# Pololu_Magnetic_Encoder.net
KiCad netlist of a schematic drawn in EAGLE
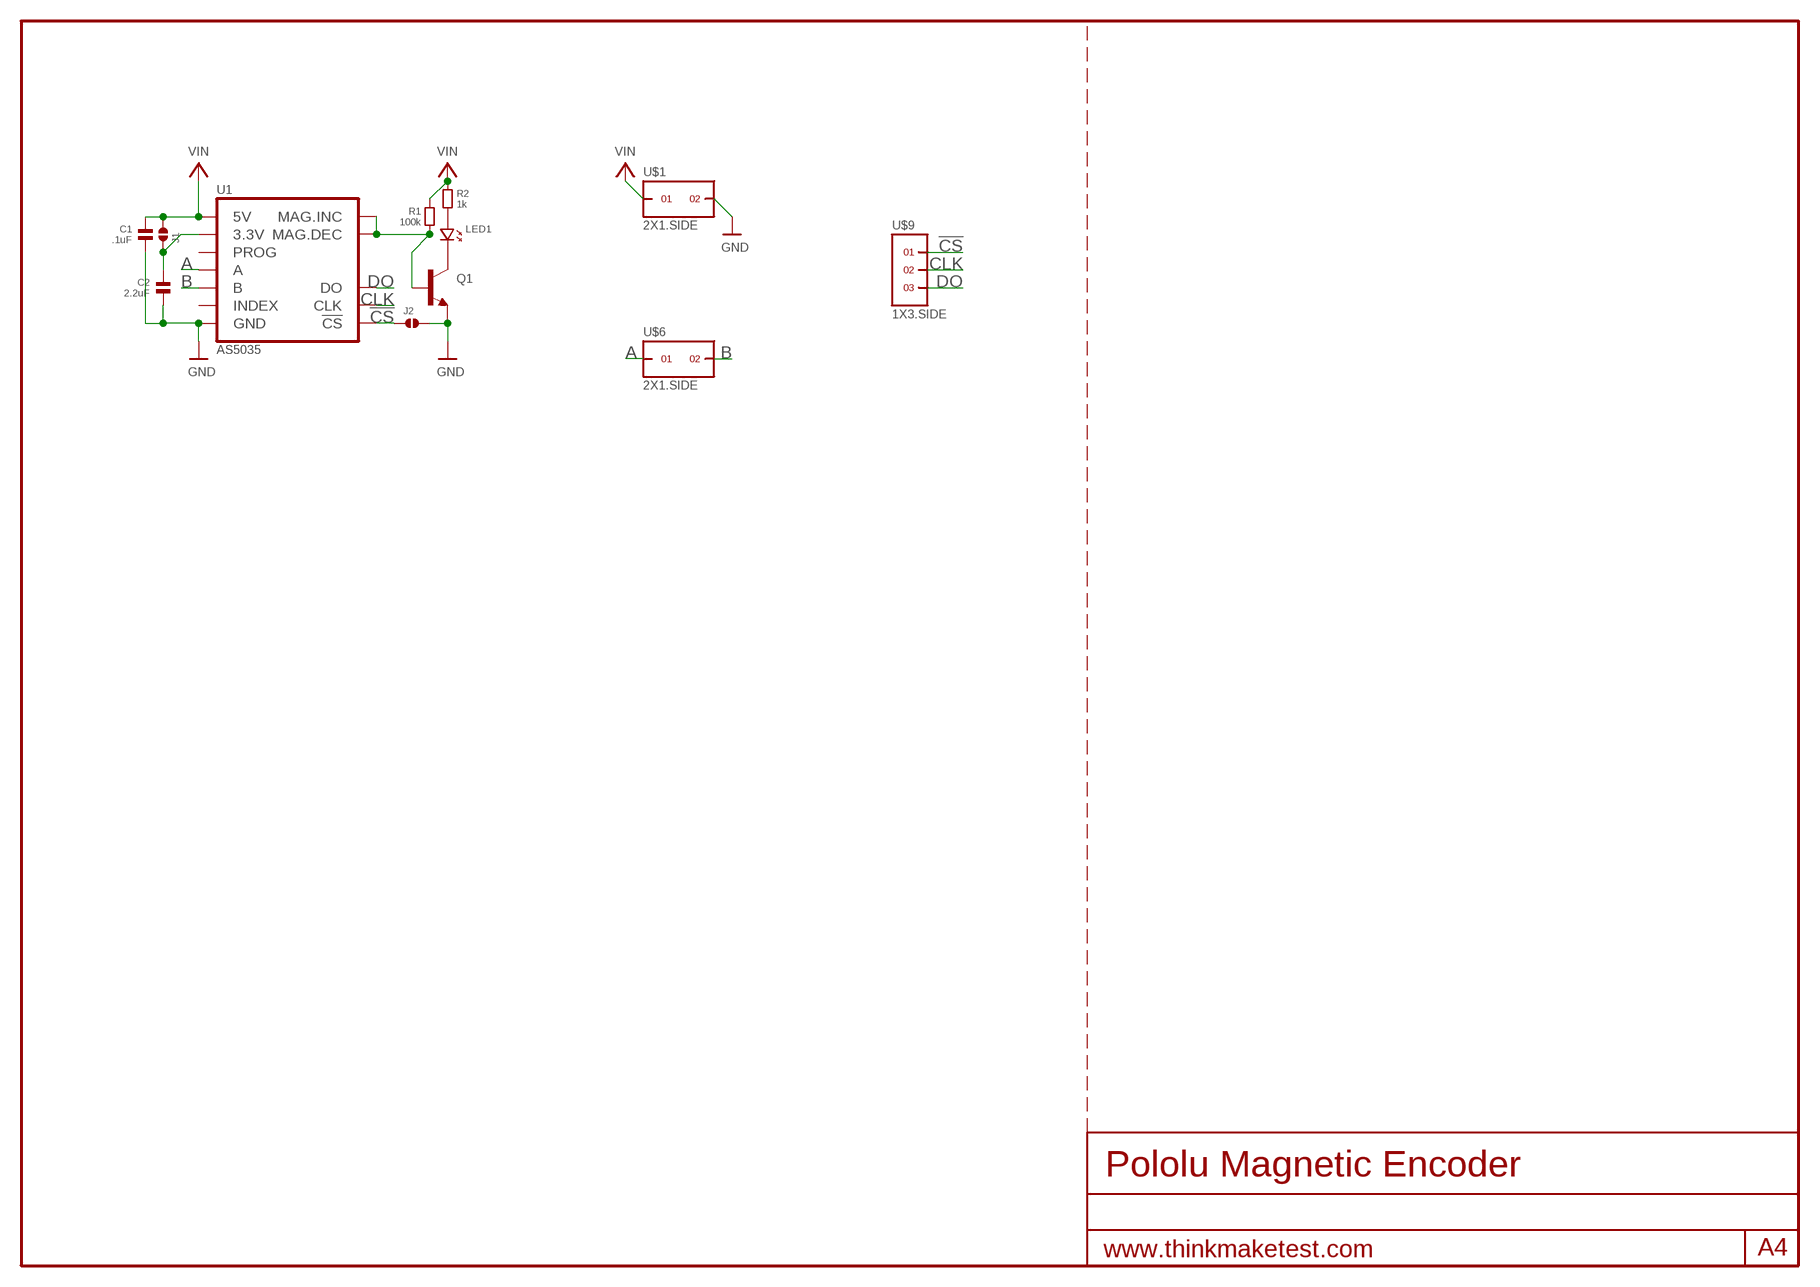
[diagram p0: schematic, sheet 1]

(export (version "E")
  (design (tool "Eeschema 10.0.6"))
  (components
    (comp (ref "C1")
      (value ".1uF")
      (footprint "eagle-import:0603")
      (libsource (lib "eagle-import") (part "CAPACITOR.0603"))
    )
    (comp (ref "C2")
      (value "2.2uF")
      (footprint "eagle-import:0603")
      (libsource (lib "eagle-import") (part "CAPACITOR.0603"))
    )
    (comp (ref "J1")
      (value "SOLDERJUMPER.2.LRG.PASTE")
      (footprint "eagle-import:2.LRG.PASTE")
      (libsource (lib "eagle-import") (part "SOLDERJUMPER.2.LRG.PASTE"))
    )
    (comp (ref "J2")
      (value "SOLDERJUMPER.2.LRG.PASTE")
      (footprint "eagle-import:2.LRG.PASTE")
      (libsource (lib "eagle-import") (part "SOLDERJUMPER.2.LRG.PASTE"))
    )
    (comp (ref "LED1")
      (value "LED.0603")
      (footprint "eagle-import:0603.LED")
      (libsource (lib "eagle-import") (part "LED.0603"))
    )
    (comp (ref "Q1")
      (value "TRANSISTOR_NPN")
      (footprint "eagle-import:SOT23-R")
      (libsource (lib "eagle-import") (part "TRANSISTOR_NPN"))
    )
    (comp (ref "R1")
      (value "100k")
      (footprint "eagle-import:0603")
      (libsource (lib "eagle-import") (part "RESISTOR.0603"))
    )
    (comp (ref "R2")
      (value "1k")
      (footprint "eagle-import:0603")
      (libsource (lib "eagle-import") (part "RESISTOR.0603"))
    )
    (comp (ref "U$1")
      (value "2X1.SIDE")
      (footprint "eagle-import:2X1.SIDE")
      (libsource (lib "eagle-import") (part "2X1.SIDE"))
    )
    (comp (ref "U$6")
      (value "2X1.SIDE")
      (footprint "eagle-import:2X1.SIDE")
      (libsource (lib "eagle-import") (part "2X1.SIDE"))
    )
    (comp (ref "U$9")
      (value "1X3.SIDE")
      (footprint "eagle-import:1X3.SIDE")
      (libsource (lib "eagle-import") (part "1X3.SIDE"))
    )
    (comp (ref "U1")
      (value "AS5035")
      (footprint "eagle-import:SSOP16")
      (libsource (lib "eagle-import") (part "AS5035"))
    )
  )
  (nets
    (net (code "1") (name "/A") (class "Default")
      (node (ref "U$6") (pin "1") (pinfunction "1_1") (pintype "bidirectional"))
      (node (ref "U1") (pin "3") (pinfunction "A_3") (pintype "bidirectional"))
    )
    (net (code "2") (name "/B") (class "Default")
      (node (ref "U$6") (pin "2") (pinfunction "2_2") (pintype "bidirectional"))
      (node (ref "U1") (pin "4") (pinfunction "B_4") (pintype "bidirectional"))
    )
    (net (code "3") (name "/CLK") (class "Default")
      (node (ref "U$9") (pin "2") (pinfunction "2_2") (pintype "bidirectional"))
      (node (ref "U1") (pin "10") (pinfunction "CLK_10") (pintype "bidirectional"))
    )
    (net (code "4") (name "/DO") (class "Default")
      (node (ref "U$9") (pin "3") (pinfunction "3_3") (pintype "bidirectional"))
      (node (ref "U1") (pin "9") (pinfunction "DO_9") (pintype "bidirectional"))
    )
    (net (code "5") (name "/~{CS}") (class "Default")
      (node (ref "J2") (pin "1") (pinfunction "1_1") (pintype "bidirectional"))
      (node (ref "U$9") (pin "1") (pinfunction "1_1") (pintype "bidirectional"))
      (node (ref "U1") (pin "11") (pinfunction "~{CS}_11") (pintype "bidirectional"))
    )
    (net (code "6") (name "GND") (class "Default")
      (node (ref "C1") (pin "2") (pinfunction "2_2") (pintype "bidirectional"))
      (node (ref "C2") (pin "2") (pinfunction "2_2") (pintype "bidirectional"))
      (node (ref "J2") (pin "2") (pinfunction "2_2") (pintype "bidirectional"))
      (node (ref "Q1") (pin "2") (pinfunction "E_2") (pintype "passive"))
      (node (ref "U$1") (pin "2") (pinfunction "2_2") (pintype "bidirectional"))
      (node (ref "U1") (pin "7") (pinfunction "GND_7") (pintype "bidirectional"))
    )
    (net (code "7") (name "Net-(LED1-1)") (class "Default")
      (node (ref "LED1") (pin "P$1") (pinfunction "1_P$1") (pintype "bidirectional"))
      (node (ref "R2") (pin "2") (pinfunction "2_2") (pintype "bidirectional"))
    )
    (net (code "8") (name "Net-(LED1-2)") (class "Default")
      (node (ref "LED1") (pin "P$2") (pinfunction "2_P$2") (pintype "bidirectional"))
      (node (ref "Q1") (pin "3") (pinfunction "C_3") (pintype "passive"))
    )
    (net (code "9") (name "Net-(Q1-B)") (class "Default")
      (node (ref "Q1") (pin "1") (pinfunction "B_1") (pintype "passive"))
      (node (ref "R1") (pin "2") (pinfunction "2_2") (pintype "bidirectional"))
      (node (ref "U1") (pin "1") (pinfunction "MAG.INC_1") (pintype "bidirectional"))
      (node (ref "U1") (pin "2") (pinfunction "MAG.DEC_2") (pintype "bidirectional"))
    )
    (net (code "10") (name "Net-(U1-3.3V)") (class "Default")
      (node (ref "C2") (pin "1") (pinfunction "1_1") (pintype "bidirectional"))
      (node (ref "J1") (pin "1") (pinfunction "1_1") (pintype "bidirectional"))
      (node (ref "U1") (pin "15") (pinfunction "3.3V_15") (pintype "bidirectional"))
    )
    (net (code "11") (name "VIN") (class "Default")
      (node (ref "C1") (pin "1") (pinfunction "1_1") (pintype "bidirectional"))
      (node (ref "J1") (pin "2") (pinfunction "2_2") (pintype "bidirectional"))
      (node (ref "R1") (pin "1") (pinfunction "1_1") (pintype "bidirectional"))
      (node (ref "R2") (pin "1") (pinfunction "1_1") (pintype "bidirectional"))
      (node (ref "U$1") (pin "1") (pinfunction "1_1") (pintype "bidirectional"))
      (node (ref "U1") (pin "16") (pinfunction "5V_16") (pintype "bidirectional"))
    )
    (net (code "12") (name "unconnected-(U1-INDEX-Pad6)") (class "Default")
      (node (ref "U1") (pin "6") (pinfunction "INDEX_6") (pintype "bidirectional"))
    )
    (net (code "13") (name "unconnected-(U1-PROG-Pad8)") (class "Default")
      (node (ref "U1") (pin "8") (pinfunction "PROG_8") (pintype "bidirectional"))
    )
  )
)
